# hb100.net
KiCad netlist of a schematic drawn in EAGLE
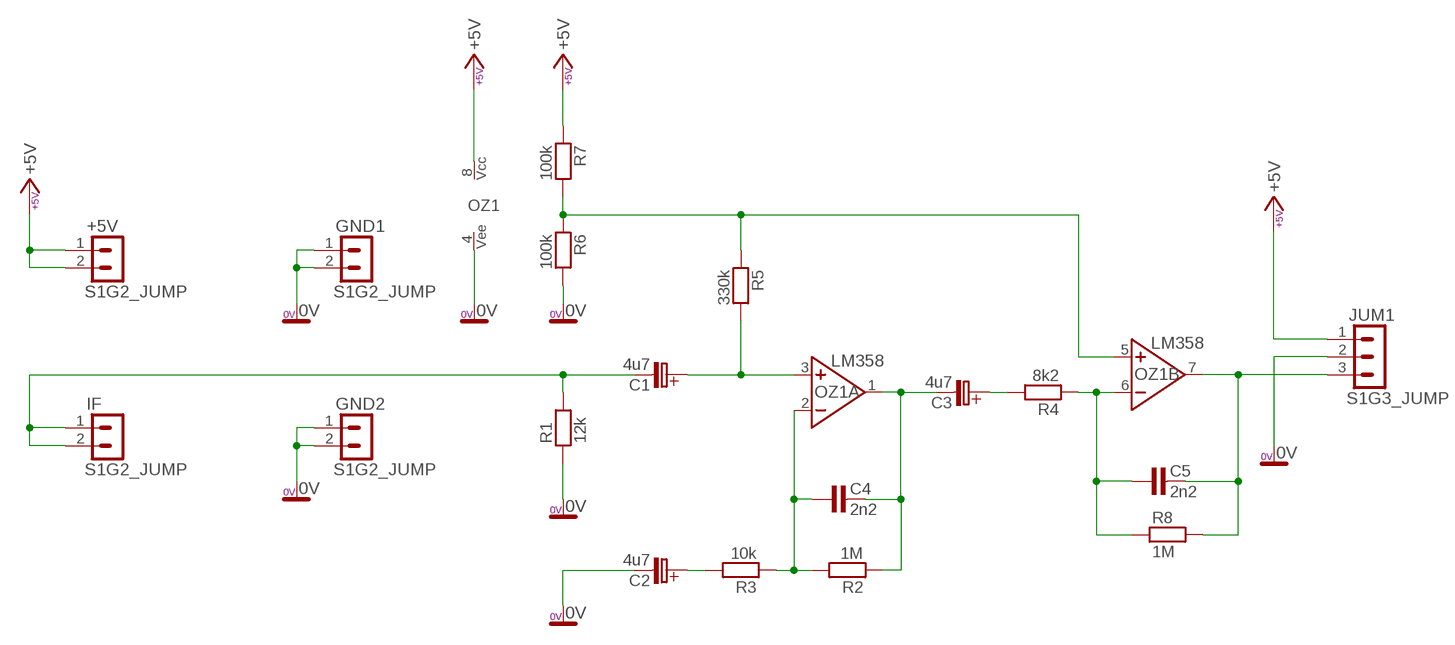
[diagram p0: schematic, sheet 1]

(export (version "E")
  (design (tool "Eeschema 10.0.6"))
  (components
    (comp (ref "+5V")
      (value "S1G2_JUMP")
      (footprint "eagle-import:S1G2_JUM")
      (libsource (lib "eagle-import") (part "S1G2_JUMP"))
    )
    (comp (ref "C1")
      (value "4u7")
      (footprint "eagle-import:C-EL_3,5")
      (libsource (lib "eagle-import") (part "C-ELEKTROLYT_3,5"))
    )
    (comp (ref "C2")
      (value "4u7")
      (footprint "eagle-import:C-EL_3,5")
      (libsource (lib "eagle-import") (part "C-ELEKTROLYT_3,5"))
    )
    (comp (ref "C3")
      (value "4u7")
      (footprint "eagle-import:C-EL_3,5")
      (libsource (lib "eagle-import") (part "C-ELEKTROLYT_3,5"))
    )
    (comp (ref "C4")
      (value "2n2")
      (footprint "eagle-import:C-5")
      (libsource (lib "eagle-import") (part "C-KERAMIK_5"))
    )
    (comp (ref "C5")
      (value "2n2")
      (footprint "eagle-import:C-5")
      (libsource (lib "eagle-import") (part "C-KERAMIK_5"))
    )
    (comp (ref "GND1")
      (value "S1G2_JUMP")
      (footprint "eagle-import:S1G2_JUM")
      (libsource (lib "eagle-import") (part "S1G2_JUMP"))
    )
    (comp (ref "GND2")
      (value "S1G2_JUMP")
      (footprint "eagle-import:S1G2_JUM")
      (libsource (lib "eagle-import") (part "S1G2_JUMP"))
    )
    (comp (ref "IF")
      (value "S1G2_JUMP")
      (footprint "eagle-import:S1G2_JUM")
      (libsource (lib "eagle-import") (part "S1G2_JUMP"))
    )
    (comp (ref "JUM1")
      (value "S1G3_JUMP")
      (footprint "eagle-import:S1G3_JUM")
      (libsource (lib "eagle-import") (part "S1G3_JUMP"))
    )
    (comp (ref "OZ1")
      (value "LM358")
      (footprint "eagle-import:DIL8")
      (libsource (lib "eagle-import") (part "LM358"))
    )
    (comp (ref "R1")
      (value "12k")
      (footprint "eagle-import:R-7,5")
      (libsource (lib "eagle-import") (part "R_7,5"))
    )
    (comp (ref "R2")
      (value "1M")
      (footprint "eagle-import:R-7,5")
      (libsource (lib "eagle-import") (part "R_7,5"))
    )
    (comp (ref "R3")
      (value "10k")
      (footprint "eagle-import:R-7,5")
      (libsource (lib "eagle-import") (part "R_7,5"))
    )
    (comp (ref "R4")
      (value "8k2")
      (footprint "eagle-import:R-7,5")
      (libsource (lib "eagle-import") (part "R_7,5"))
    )
    (comp (ref "R5")
      (value "330k")
      (footprint "eagle-import:R-7,5")
      (libsource (lib "eagle-import") (part "R_7,5"))
    )
    (comp (ref "R6")
      (value "100k")
      (footprint "eagle-import:R-7,5")
      (libsource (lib "eagle-import") (part "R_7,5"))
    )
    (comp (ref "R7")
      (value "100k")
      (footprint "eagle-import:R-7,5")
      (libsource (lib "eagle-import") (part "R_7,5"))
    )
    (comp (ref "R8")
      (value "1M")
      (footprint "eagle-import:R-7,5")
      (libsource (lib "eagle-import") (part "R_7,5"))
    )
  )
  (nets
    (net (code "1") (name "+5V") (class "Default")
      (node (ref "+5V") (pin "1") (pinfunction "1_1") (pintype "passive"))
      (node (ref "+5V") (pin "2") (pinfunction "2_2") (pintype "passive"))
      (node (ref "JUM1") (pin "1") (pinfunction "1_1") (pintype "passive"))
      (node (ref "OZ1") (pin "8") (pinfunction "VCC_8") (pintype "power_in"))
      (node (ref "R7") (pin "1") (pinfunction "1_1") (pintype "passive"))
    )
    (net (code "2") (name "0V") (class "Default")
      (node (ref "C2") (pin "C-") (pinfunction "C_EL-_C-") (pintype "passive"))
      (node (ref "GND1") (pin "1") (pinfunction "1_1") (pintype "passive"))
      (node (ref "GND1") (pin "2") (pinfunction "2_2") (pintype "passive"))
      (node (ref "GND2") (pin "1") (pinfunction "1_1") (pintype "passive"))
      (node (ref "GND2") (pin "2") (pinfunction "2_2") (pintype "passive"))
      (node (ref "JUM1") (pin "2") (pinfunction "2_2") (pintype "passive"))
      (node (ref "OZ1") (pin "4") (pinfunction "VEE_4") (pintype "power_in"))
      (node (ref "R1") (pin "1") (pinfunction "1_1") (pintype "passive"))
      (node (ref "R6") (pin "2") (pinfunction "2_2") (pintype "passive"))
    )
    (net (code "3") (name "Net-(C1-C_EL+)") (class "Default")
      (node (ref "C1") (pin "C+") (pinfunction "C_EL+_C+") (pintype "passive"))
      (node (ref "OZ1") (pin "3") (pinfunction "NEIN+_3") (pintype "input"))
      (node (ref "R5") (pin "2") (pinfunction "2_2") (pintype "passive"))
    )
    (net (code "4") (name "Net-(C1-C_EL-)") (class "Default")
      (node (ref "C1") (pin "C-") (pinfunction "C_EL-_C-") (pintype "passive"))
      (node (ref "IF") (pin "1") (pinfunction "1_1") (pintype "passive"))
      (node (ref "IF") (pin "2") (pinfunction "2_2") (pintype "passive"))
      (node (ref "R1") (pin "2") (pinfunction "2_2") (pintype "passive"))
    )
    (net (code "5") (name "Net-(C2-C_EL+)") (class "Default")
      (node (ref "C2") (pin "C+") (pinfunction "C_EL+_C+") (pintype "passive"))
      (node (ref "R3") (pin "2") (pinfunction "2_2") (pintype "passive"))
    )
    (net (code "6") (name "Net-(C3-C_EL+)") (class "Default")
      (node (ref "C3") (pin "C+") (pinfunction "C_EL+_C+") (pintype "passive"))
      (node (ref "R4") (pin "2") (pinfunction "2_2") (pintype "passive"))
    )
    (net (code "7") (name "Net-(C3-C_EL-)") (class "Default")
      (node (ref "C3") (pin "C-") (pinfunction "C_EL-_C-") (pintype "passive"))
      (node (ref "C4") (pin "2") (pinfunction "2_2") (pintype "passive"))
      (node (ref "OZ1") (pin "1") (pinfunction "VYSTUP_1") (pintype "output"))
      (node (ref "R2") (pin "1") (pinfunction "1_1") (pintype "passive"))
    )
    (net (code "8") (name "Net-(OZ1A-IN-)") (class "Default")
      (node (ref "C4") (pin "1") (pinfunction "1_1") (pintype "passive"))
      (node (ref "OZ1") (pin "2") (pinfunction "IN-_2") (pintype "input"))
      (node (ref "R2") (pin "2") (pinfunction "2_2") (pintype "passive"))
      (node (ref "R3") (pin "1") (pinfunction "1_1") (pintype "passive"))
    )
    (net (code "9") (name "Net-(OZ1B-IN-)") (class "Default")
      (node (ref "C5") (pin "1") (pinfunction "1_1") (pintype "passive"))
      (node (ref "OZ1") (pin "6") (pinfunction "IN-_6") (pintype "input"))
      (node (ref "R4") (pin "1") (pinfunction "1_1") (pintype "passive"))
      (node (ref "R8") (pin "1") (pinfunction "1_1") (pintype "passive"))
    )
    (net (code "10") (name "Net-(OZ1B-NEIN+)") (class "Default")
      (node (ref "OZ1") (pin "5") (pinfunction "NEIN+_5") (pintype "input"))
      (node (ref "R5") (pin "1") (pinfunction "1_1") (pintype "passive"))
      (node (ref "R6") (pin "1") (pinfunction "1_1") (pintype "passive"))
      (node (ref "R7") (pin "2") (pinfunction "2_2") (pintype "passive"))
    )
    (net (code "11") (name "Net-(OZ1B-VYSTUP)") (class "Default")
      (node (ref "C5") (pin "2") (pinfunction "2_2") (pintype "passive"))
      (node (ref "JUM1") (pin "3") (pinfunction "3_3") (pintype "passive"))
      (node (ref "OZ1") (pin "7") (pinfunction "VYSTUP_7") (pintype "output"))
      (node (ref "R8") (pin "2") (pinfunction "2_2") (pintype "passive"))
    )
  )
)
